# voltreg.net
KiCad netlist of a schematic drawn in EAGLE
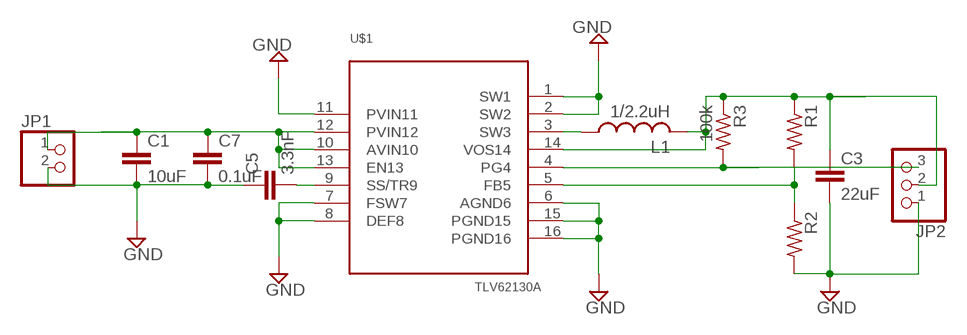
[diagram p0: schematic, sheet 1]

(export (version "E")
  (design (tool "Eeschema 10.0.6"))
  (components
    (comp (ref "C1")
      (value "10uF")
      (footprint "eagle-import:C0805")
      (libsource (lib "eagle-import") (part "C-EUC0805"))
    )
    (comp (ref "C3")
      (value "22uF")
      (footprint "eagle-import:C0805")
      (libsource (lib "eagle-import") (part "C-EUC0805"))
    )
    (comp (ref "C5")
      (value "3.3nF")
      (footprint "eagle-import:C0805")
      (libsource (lib "eagle-import") (part "C-EUC0805"))
    )
    (comp (ref "C7")
      (value "0.1uF")
      (footprint "eagle-import:C0805")
      (libsource (lib "eagle-import") (part "C-EUC0805"))
    )
    (comp (ref "JP1")
      (value "PINHD-1X2")
      (footprint "eagle-import:1X02")
      (libsource (lib "eagle-import") (part "PINHD-1X2"))
    )
    (comp (ref "JP2")
      (value "PINHD-1X3")
      (footprint "eagle-import:1X03")
      (libsource (lib "eagle-import") (part "PINHD-1X3"))
    )
    (comp (ref "L1")
      (value "1/2.2uH")
      (footprint "eagle-import:L3225M")
      (libsource (lib "eagle-import") (part "L-USL3225M"))
    )
    (comp (ref "R1")
      (value "R-US_R0805")
      (footprint "eagle-import:R0805")
      (libsource (lib "eagle-import") (part "R-US_R0805"))
    )
    (comp (ref "R2")
      (value "R-US_R0805")
      (footprint "eagle-import:R0805")
      (libsource (lib "eagle-import") (part "R-US_R0805"))
    )
    (comp (ref "R3")
      (value "100k")
      (footprint "eagle-import:R0805")
      (libsource (lib "eagle-import") (part "R-US_R0805"))
    )
    (comp (ref "U$1")
      (value "TLV62130A")
      (footprint "eagle-import:TLV62130A")
      (libsource (lib "eagle-import") (part "TLV62130A"))
    )
  )
  (nets
    (net (code "1") (name "GND") (class "Default")
      (node (ref "C1") (pin "2") (pinfunction "2_2") (pintype "passive"))
      (node (ref "C3") (pin "2") (pinfunction "2_2") (pintype "passive"))
      (node (ref "C5") (pin "1") (pinfunction "1_1") (pintype "passive"))
      (node (ref "C7") (pin "2") (pinfunction "2_2") (pintype "passive"))
      (node (ref "JP1") (pin "2") (pinfunction "2_2") (pintype "passive"))
      (node (ref "JP2") (pin "1") (pinfunction "1_1") (pintype "passive"))
      (node (ref "R2") (pin "2") (pinfunction "2_2") (pintype "passive"))
      (node (ref "U$1") (pin "1") (pinfunction "SW1_1") (pintype "input"))
      (node (ref "U$1") (pin "11") (pinfunction "PVIN11_11") (pintype "input"))
      (node (ref "U$1") (pin "15") (pinfunction "PGND15_15") (pintype "power_in"))
      (node (ref "U$1") (pin "16") (pinfunction "PGND16_16") (pintype "power_in"))
      (node (ref "U$1") (pin "2") (pinfunction "SW2_2") (pintype "input"))
      (node (ref "U$1") (pin "6") (pinfunction "AGND6_6") (pintype "power_in"))
      (node (ref "U$1") (pin "7") (pinfunction "FSW7_7") (pintype "input"))
      (node (ref "U$1") (pin "8") (pinfunction "DEF8_8") (pintype "input"))
    )
    (net (code "2") (name "Net-(U$1-AVIN10)") (class "Default")
      (node (ref "C1") (pin "1") (pinfunction "1_1") (pintype "passive"))
      (node (ref "C7") (pin "1") (pinfunction "1_1") (pintype "passive"))
      (node (ref "JP1") (pin "1") (pinfunction "1_1") (pintype "passive"))
      (node (ref "U$1") (pin "10") (pinfunction "AVIN10_10") (pintype "input"))
      (node (ref "U$1") (pin "12") (pinfunction "PVIN12_12") (pintype "input"))
      (node (ref "U$1") (pin "13") (pinfunction "EN13_13") (pintype "input"))
    )
    (net (code "3") (name "Net-(U$1-FB5)") (class "Default")
      (node (ref "R1") (pin "2") (pinfunction "2_2") (pintype "passive"))
      (node (ref "R2") (pin "1") (pinfunction "1_1") (pintype "passive"))
      (node (ref "U$1") (pin "5") (pinfunction "FB5_5") (pintype "input"))
    )
    (net (code "4") (name "Net-(U$1-PG4)") (class "Default")
      (node (ref "JP2") (pin "3") (pinfunction "3_3") (pintype "passive"))
      (node (ref "R3") (pin "2") (pinfunction "2_2") (pintype "passive"))
      (node (ref "U$1") (pin "4") (pinfunction "PG4_4") (pintype "input"))
    )
    (net (code "5") (name "Net-(U$1-SS{slash}TR9)") (class "Default")
      (node (ref "C5") (pin "2") (pinfunction "2_2") (pintype "passive"))
      (node (ref "U$1") (pin "9") (pinfunction "SS/TR9_9") (pintype "input"))
    )
    (net (code "6") (name "Net-(U$1-SW3)") (class "Default")
      (node (ref "L1") (pin "1") (pinfunction "1_1") (pintype "passive"))
      (node (ref "U$1") (pin "3") (pinfunction "SW3_3") (pintype "input"))
    )
    (net (code "7") (name "Net-(U$1-VOS14)") (class "Default")
      (node (ref "C3") (pin "1") (pinfunction "1_1") (pintype "passive"))
      (node (ref "JP2") (pin "2") (pinfunction "2_2") (pintype "passive"))
      (node (ref "L1") (pin "2") (pinfunction "2_2") (pintype "passive"))
      (node (ref "R1") (pin "1") (pinfunction "1_1") (pintype "passive"))
      (node (ref "R3") (pin "1") (pinfunction "1_1") (pintype "passive"))
      (node (ref "U$1") (pin "14") (pinfunction "VOS14_14") (pintype "input"))
    )
  )
)
